# batteryCase.net
KiCad netlist of a schematic drawn in EAGLE
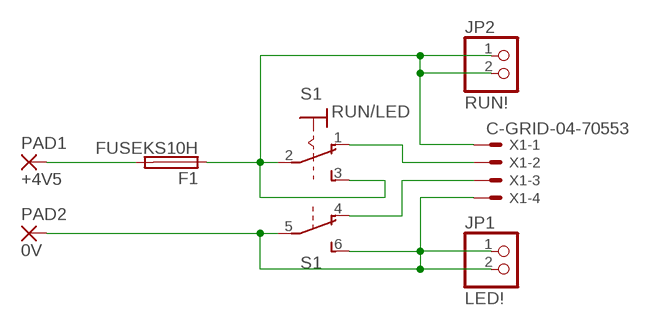
[diagram p0: schematic, sheet 1]

(export (version "E")
  (design (tool "Eeschema 10.0.6"))
  (components
    (comp (ref "F1")
      (value "FUSEKS10H")
      (footprint "eagle-import:KS10H")
      (libsource (lib "eagle-import") (part "FUSEKS10H"))
    )
    (comp (ref "JP1")
      (value "LED!")
      (footprint "eagle-import:1X02_90")
      (libsource (lib "eagle-import") (part "PINHD-1X2/90"))
    )
    (comp (ref "JP2")
      (value "RUN!")
      (footprint "eagle-import:1X02_90")
      (libsource (lib "eagle-import") (part "PINHD-1X2/90"))
    )
    (comp (ref "PAD1")
      (value "+4V5")
      (footprint "eagle-import:SMD2,54-5,08")
      (libsource (lib "eagle-import") (part "SMD5"))
    )
    (comp (ref "PAD2")
      (value "0V")
      (footprint "eagle-import:SMD2,54-5,08")
      (libsource (lib "eagle-import") (part "SMD5"))
    )
    (comp (ref "S1")
      (value "RUN/LED")
      (footprint "eagle-import:M9040P2")
      (libsource (lib "eagle-import") (part "M9040P2"))
    )
    (comp (ref "X1")
      (value "C-GRID-04-70553")
      (footprint "eagle-import:70553-04")
      (libsource (lib "eagle-import") (part "C-GRID-04-70553"))
    )
  )
  (nets
    (net (code "1") (name "Net-(PAD1-P)") (class "Default")
      (node (ref "F1") (pin "2") (pinfunction "2_2") (pintype "passive"))
      (node (ref "PAD1") (pin "1") (pinfunction "P_1") (pintype "passive"))
    )
    (net (code "2") (name "Net-(PAD2-P)") (class "Default")
      (node (ref "JP1") (pin "1") (pinfunction "1_1") (pintype "passive"))
      (node (ref "JP1") (pin "2") (pinfunction "2_2") (pintype "passive"))
      (node (ref "PAD2") (pin "1") (pinfunction "P_1") (pintype "passive"))
      (node (ref "S1") (pin "5") (pinfunction "P_5") (pintype "passive"))
      (node (ref "S1") (pin "6") (pinfunction "S_6") (pintype "passive"))
      (node (ref "X1") (pin "4") (pinfunction "S_4") (pintype "passive"))
    )
    (net (code "3") (name "Net-(S1A-O)") (class "Default")
      (node (ref "S1") (pin "1") (pinfunction "O_1") (pintype "passive"))
      (node (ref "X1") (pin "2") (pinfunction "S_2") (pintype "passive"))
    )
    (net (code "4") (name "Net-(S1A-P)") (class "Default")
      (node (ref "F1") (pin "1") (pinfunction "1_1") (pintype "passive"))
      (node (ref "JP2") (pin "1") (pinfunction "1_1") (pintype "passive"))
      (node (ref "JP2") (pin "2") (pinfunction "2_2") (pintype "passive"))
      (node (ref "S1") (pin "2") (pinfunction "P_2") (pintype "passive"))
      (node (ref "S1") (pin "3") (pinfunction "S_3") (pintype "passive"))
      (node (ref "X1") (pin "1") (pinfunction "S_1") (pintype "passive"))
    )
    (net (code "5") (name "Net-(S1B-O)") (class "Default")
      (node (ref "S1") (pin "4") (pinfunction "O_4") (pintype "passive"))
      (node (ref "X1") (pin "3") (pinfunction "S_3") (pintype "passive"))
    )
  )
)
